# detector.net
KiCad netlist of a schematic drawn in EAGLE
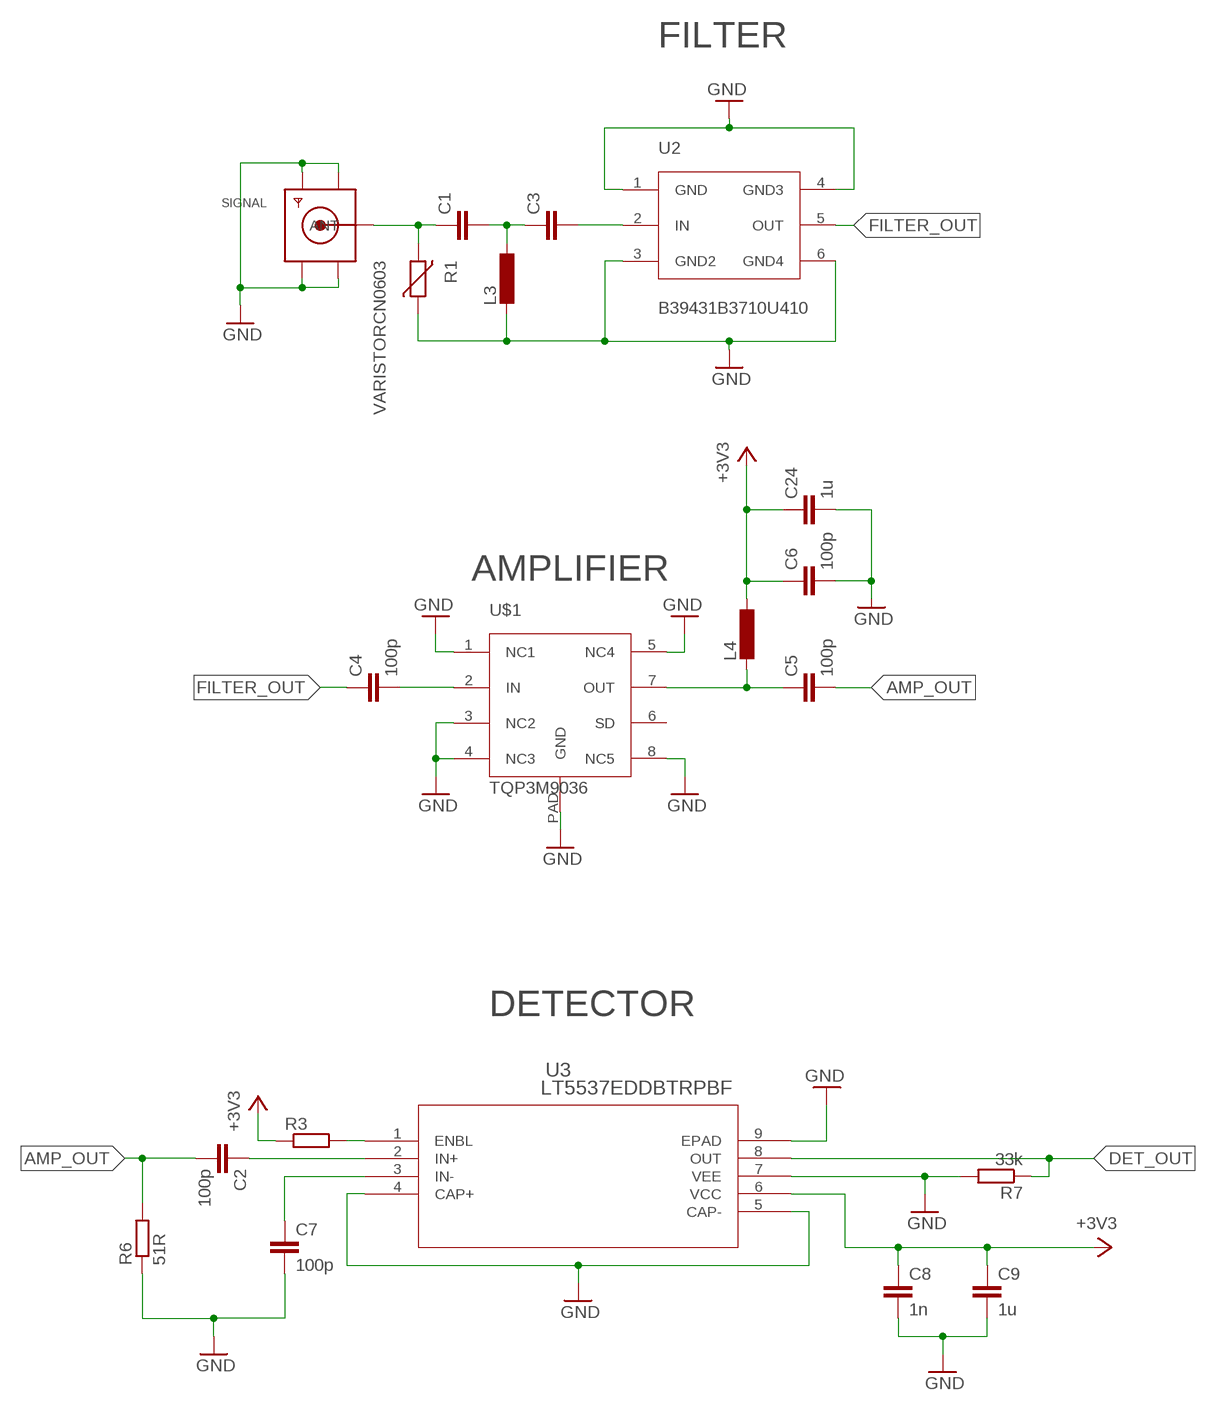
[diagram p0: schematic, sheet 1]

(export (version "E")
  (design (tool "Eeschema 10.0.6"))
  (components
    (comp (ref "C1")
      (value "C-EUC0603")
      (footprint "eagle-import:C0603")
      (libsource (lib "eagle-import") (part "C-EUC0603"))
    )
    (comp (ref "C2")
      (value "100p")
      (footprint "eagle-import:C0603")
      (libsource (lib "eagle-import") (part "C-EUC0603"))
    )
    (comp (ref "C3")
      (value "C-EUC0603")
      (footprint "eagle-import:C0603")
      (libsource (lib "eagle-import") (part "C-EUC0603"))
    )
    (comp (ref "C4")
      (value "100p")
      (footprint "eagle-import:C0603")
      (libsource (lib "eagle-import") (part "C-EUC0603"))
    )
    (comp (ref "C5")
      (value "100p")
      (footprint "eagle-import:C0603")
      (libsource (lib "eagle-import") (part "C-EUC0603"))
    )
    (comp (ref "C6")
      (value "100p")
      (footprint "eagle-import:C0603")
      (libsource (lib "eagle-import") (part "C-EUC0603"))
    )
    (comp (ref "C7")
      (value "100p")
      (footprint "eagle-import:C0603")
      (libsource (lib "eagle-import") (part "C-EUC0603"))
    )
    (comp (ref "C8")
      (value "1n")
      (footprint "eagle-import:C0603")
      (libsource (lib "eagle-import") (part "C-EUC0603"))
    )
    (comp (ref "C9")
      (value "1u")
      (footprint "eagle-import:C0603")
      (libsource (lib "eagle-import") (part "C-EUC0603"))
    )
    (comp (ref "C24")
      (value "1u")
      (footprint "eagle-import:C0603")
      (libsource (lib "eagle-import") (part "C-EUC0603"))
    )
    (comp (ref "L3")
      (value "L-EUL2012C")
      (footprint "eagle-import:L2012C")
      (libsource (lib "eagle-import") (part "L-EUL2012C"))
    )
    (comp (ref "L4")
      (value "L-EUL2012C")
      (footprint "eagle-import:L2012C")
      (libsource (lib "eagle-import") (part "L-EUL2012C"))
    )
    (comp (ref "R1")
      (value "VARISTORCN0603")
      (footprint "eagle-import:CT_CN0603")
      (libsource (lib "eagle-import") (part "VARISTORCN0603"))
    )
    (comp (ref "R3")
      (value "R-EU_R0603")
      (footprint "eagle-import:R0603")
      (libsource (lib "eagle-import") (part "R-EU_R0603"))
    )
    (comp (ref "R6")
      (value "51R")
      (footprint "eagle-import:R0603")
      (libsource (lib "eagle-import") (part "R-EU_R0603"))
    )
    (comp (ref "R7")
      (value "33k")
      (footprint "eagle-import:R0603")
      (libsource (lib "eagle-import") (part "R-EU_R0603"))
    )
    (comp (ref "SIGNAL")
      (value "SMACONNECTOR_EDGE")
      (footprint "eagle-import:SMA_EDGELAUNCH")
      (libsource (lib "eagle-import") (part "SMACONNECTOR_EDGE"))
    )
    (comp (ref "U$1")
      (value "TQP3M9036")
      (footprint "eagle-import:DFN-8_2X2")
      (libsource (lib "eagle-import") (part "TQP3M9036"))
    )
    (comp (ref "U2")
      (value "B39431B3710U410")
      (footprint "eagle-import:SON120P300X300X110-6N")
      (libsource (lib "eagle-import") (part "B39431B3710U410"))
    )
    (comp (ref "U3")
      (value "LT5537EDDBTRPBF")
      (footprint "eagle-import:DFN-8_DDB")
      (fields (field (name "MF") "Linear Technology") (field (name "MP") "LT5537EDDB#TRPBF"))
      (libsource (lib "eagle-import") (part "LT5537EDDBTRPBF"))
    )
  )
  (nets
    (net (code "1") (name "+3V3") (class "Default")
      (node (ref "C24") (pin "1") (pinfunction "1_1") (pintype "passive"))
      (node (ref "C6") (pin "1") (pinfunction "1_1") (pintype "passive"))
      (node (ref "C8") (pin "1") (pinfunction "1_1") (pintype "passive"))
      (node (ref "C9") (pin "1") (pinfunction "1_1") (pintype "passive"))
      (node (ref "L4") (pin "1") (pinfunction "1_1") (pintype "passive"))
      (node (ref "R3") (pin "1") (pinfunction "1_1") (pintype "passive"))
      (node (ref "U3") (pin "6") (pinfunction "VCC_6") (pintype "power_in"))
    )
    (net (code "2") (name "AMP_OUT") (class "Default")
      (node (ref "C2") (pin "2") (pinfunction "2_2") (pintype "passive"))
      (node (ref "C5") (pin "2") (pinfunction "2_2") (pintype "passive"))
      (node (ref "R6") (pin "2") (pinfunction "2_2") (pintype "passive"))
    )
    (net (code "3") (name "DET_OUT") (class "Default")
      (node (ref "R7") (pin "1") (pinfunction "1_1") (pintype "passive"))
      (node (ref "U3") (pin "8") (pinfunction "OUT_8") (pintype "output"))
    )
    (net (code "4") (name "FILTER_OUT") (class "Default")
      (node (ref "C4") (pin "1") (pinfunction "1_1") (pintype "passive"))
      (node (ref "U2") (pin "5") (pinfunction "OUT_5") (pintype "bidirectional"))
    )
    (net (code "5") (name "GND") (class "Default")
      (node (ref "C24") (pin "2") (pinfunction "2_2") (pintype "passive"))
      (node (ref "C6") (pin "2") (pinfunction "2_2") (pintype "passive"))
      (node (ref "C7") (pin "2") (pinfunction "2_2") (pintype "passive"))
      (node (ref "C8") (pin "2") (pinfunction "2_2") (pintype "passive"))
      (node (ref "C9") (pin "2") (pinfunction "2_2") (pintype "passive"))
      (node (ref "L3") (pin "2") (pinfunction "2_2") (pintype "passive"))
      (node (ref "R1") (pin "1") (pinfunction "1_1") (pintype "passive"))
      (node (ref "R6") (pin "1") (pinfunction "1_1") (pintype "passive"))
      (node (ref "R7") (pin "2") (pinfunction "2_2") (pintype "passive"))
      (node (ref "SIGNAL") (pin "GND@1") (pinfunction "GND4_GND@1") (pintype "power_in"))
      (node (ref "SIGNAL") (pin "GND@2") (pinfunction "GND3_GND@2") (pintype "power_in"))
      (node (ref "SIGNAL") (pin "GND@3") (pinfunction "GND2_GND@3") (pintype "power_in"))
      (node (ref "SIGNAL") (pin "GND@4") (pinfunction "GND1_GND@4") (pintype "power_in"))
      (node (ref "U$1") (pin "1") (pinfunction "NC1_1") (pintype "bidirectional"))
      (node (ref "U$1") (pin "3") (pinfunction "NC2_3") (pintype "bidirectional"))
      (node (ref "U$1") (pin "4") (pinfunction "NC3_4") (pintype "bidirectional"))
      (node (ref "U$1") (pin "5") (pinfunction "NC4_5") (pintype "bidirectional"))
      (node (ref "U$1") (pin "8") (pinfunction "NC5_8") (pintype "bidirectional"))
      (node (ref "U$1") (pin "PAD") (pinfunction "GND_PAD") (pintype "bidirectional"))
      (node (ref "U2") (pin "1") (pinfunction "GND_1") (pintype "power_in"))
      (node (ref "U2") (pin "3") (pinfunction "GND2_3") (pintype "power_in"))
      (node (ref "U2") (pin "4") (pinfunction "GND3_4") (pintype "power_in"))
      (node (ref "U2") (pin "6") (pinfunction "GND4_6") (pintype "power_in"))
      (node (ref "U3") (pin "4") (pinfunction "CAP+_4") (pintype "passive"))
      (node (ref "U3") (pin "5") (pinfunction "CAP-_5") (pintype "passive"))
      (node (ref "U3") (pin "7") (pinfunction "VEE_7") (pintype "power_in"))
      (node (ref "U3") (pin "9") (pinfunction "EPAD_9") (pintype "passive"))
    )
    (net (code "6") (name "Net-(C1-Pad2)") (class "Default")
      (node (ref "C1") (pin "2") (pinfunction "2_2") (pintype "passive"))
      (node (ref "C3") (pin "1") (pinfunction "1_1") (pintype "passive"))
      (node (ref "L3") (pin "1") (pinfunction "1_1") (pintype "passive"))
    )
    (net (code "7") (name "Net-(SIGNAL-ANT)") (class "Default")
      (node (ref "C1") (pin "1") (pinfunction "1_1") (pintype "passive"))
      (node (ref "R1") (pin "2") (pinfunction "2_2") (pintype "passive"))
      (node (ref "SIGNAL") (pin "P") (pinfunction "ANT_P") (pintype "bidirectional"))
    )
    (net (code "8") (name "Net-(U$1-IN)") (class "Default")
      (node (ref "C4") (pin "2") (pinfunction "2_2") (pintype "passive"))
      (node (ref "U$1") (pin "2") (pinfunction "IN_2") (pintype "bidirectional"))
    )
    (net (code "9") (name "Net-(U$1-OUT)") (class "Default")
      (node (ref "C5") (pin "1") (pinfunction "1_1") (pintype "passive"))
      (node (ref "L4") (pin "2") (pinfunction "2_2") (pintype "passive"))
      (node (ref "U$1") (pin "7") (pinfunction "OUT_7") (pintype "bidirectional"))
    )
    (net (code "10") (name "Net-(U2-IN)") (class "Default")
      (node (ref "C3") (pin "2") (pinfunction "2_2") (pintype "passive"))
      (node (ref "U2") (pin "2") (pinfunction "IN_2") (pintype "bidirectional"))
    )
    (net (code "11") (name "Net-(U3-ENBL)") (class "Default")
      (node (ref "R3") (pin "2") (pinfunction "2_2") (pintype "passive"))
      (node (ref "U3") (pin "1") (pinfunction "ENBL_1") (pintype "input"))
    )
    (net (code "12") (name "Net-(U3-IN+)") (class "Default")
      (node (ref "C2") (pin "1") (pinfunction "1_1") (pintype "passive"))
      (node (ref "U3") (pin "2") (pinfunction "IN+_2") (pintype "input"))
    )
    (net (code "13") (name "Net-(U3-IN-)") (class "Default")
      (node (ref "C7") (pin "1") (pinfunction "1_1") (pintype "passive"))
      (node (ref "U3") (pin "3") (pinfunction "IN-_3") (pintype "input"))
    )
    (net (code "14") (name "unconnected-(U$1-SD-Pad6)") (class "Default")
      (node (ref "U$1") (pin "6") (pinfunction "SD_6") (pintype "bidirectional"))
    )
  )
)
